# top_level.net
KiCad netlist of a schematic drawn in Altium Designer
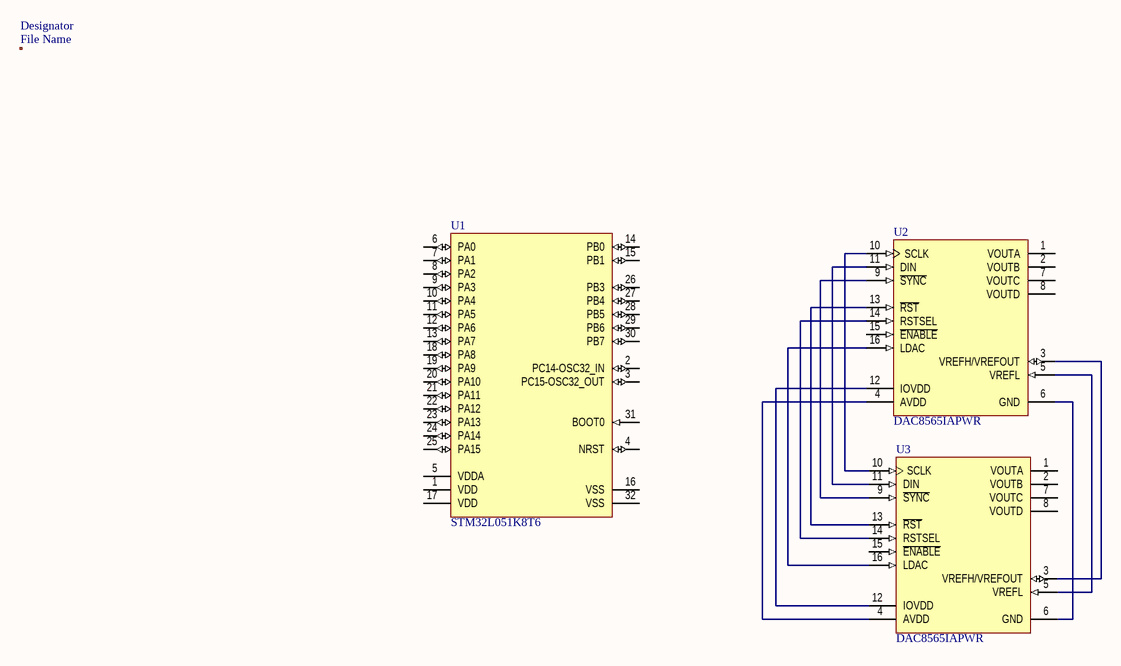
[diagram p0: top_level.SchDoc]

(export (version "E")
  (design (tool "Eeschema 10.0.6"))
  (components
    (comp (ref "U1")
      (value "STM32L051K8T6")
      (footprint "STM-LQFP32_L")
      (libsource (lib "Altium Content Vault") (part "STM-STM32L051-LQFP-32"))
    )
    (comp (ref "U2")
      (value "DAC8565IAPWR")
      (footprint "TI-PW16_L")
      (fields (field (name "MANUFACTURER") "Texas Instruments"))
      (libsource (lib "Altium Content Vault") (part "TI-DACXX65PW16"))
    )
    (comp (ref "U3")
      (value "DAC8565IAPWR")
      (footprint "TI-PW16_L")
      (fields (field (name "MANUFACTURER") "Texas Instruments"))
      (libsource (lib "Altium Content Vault") (part "TI-DACXX65PW16"))
    )
  )
  (nets
    (net (code "1") (name "Net-(U2-AVDD)") (class "Default")
      (node (ref "U2") (pin "4") (pinfunction "AVDD_4") (pintype "power_in"))
      (node (ref "U3") (pin "4") (pinfunction "AVDD_4") (pintype "power_in"))
    )
    (net (code "2") (name "Net-(U2-DIN)") (class "Default")
      (node (ref "U2") (pin "11") (pinfunction "DIN_11") (pintype "input"))
      (node (ref "U3") (pin "11") (pinfunction "DIN_11") (pintype "input"))
    )
    (net (code "3") (name "Net-(U2-GND)") (class "Default")
      (node (ref "U2") (pin "6") (pinfunction "GND_6") (pintype "power_in"))
      (node (ref "U3") (pin "6") (pinfunction "GND_6") (pintype "power_in"))
    )
    (net (code "4") (name "Net-(U2-IOVDD)") (class "Default")
      (node (ref "U2") (pin "12") (pinfunction "IOVDD_12") (pintype "power_in"))
      (node (ref "U3") (pin "12") (pinfunction "IOVDD_12") (pintype "power_in"))
    )
    (net (code "5") (name "Net-(U2-LDAC)") (class "Default")
      (node (ref "U2") (pin "16") (pinfunction "LDAC_16") (pintype "input"))
      (node (ref "U3") (pin "16") (pinfunction "LDAC_16") (pintype "input"))
    )
    (net (code "6") (name "Net-(U2-RSTSEL)") (class "Default")
      (node (ref "U2") (pin "14") (pinfunction "RSTSEL_14") (pintype "input"))
      (node (ref "U3") (pin "14") (pinfunction "RSTSEL_14") (pintype "input"))
    )
    (net (code "7") (name "Net-(U2-SCLK)") (class "Default")
      (node (ref "U2") (pin "10") (pinfunction "SCLK_10") (pintype "input"))
      (node (ref "U3") (pin "10") (pinfunction "SCLK_10") (pintype "input"))
    )
    (net (code "8") (name "Net-(U2-VREFH{slash}VREFOUT)") (class "Default")
      (node (ref "U2") (pin "3") (pinfunction "VREFH/VREFOUT_3") (pintype "bidirectional"))
      (node (ref "U3") (pin "3") (pinfunction "VREFH/VREFOUT_3") (pintype "bidirectional"))
    )
    (net (code "9") (name "Net-(U2-VREFL)") (class "Default")
      (node (ref "U2") (pin "5") (pinfunction "VREFL_5") (pintype "input"))
      (node (ref "U3") (pin "5") (pinfunction "VREFL_5") (pintype "input"))
    )
    (net (code "10") (name "Net-(U2-~{RST})") (class "Default")
      (node (ref "U2") (pin "13") (pinfunction "~{RST}_13") (pintype "input"))
      (node (ref "U3") (pin "13") (pinfunction "~{RST}_13") (pintype "input"))
    )
    (net (code "11") (name "Net-(U2-~{SYNC})") (class "Default")
      (node (ref "U2") (pin "9") (pinfunction "~{SYNC}_9") (pintype "input"))
      (node (ref "U3") (pin "9") (pinfunction "~{SYNC}_9") (pintype "input"))
    )
    (net (code "12") (name "unconnected-(U1-BOOT0-Pad31)") (class "Default")
      (node (ref "U1") (pin "31") (pinfunction "BOOT0_31") (pintype "input"))
    )
    (net (code "13") (name "unconnected-(U1-NRST-Pad4)") (class "Default")
      (node (ref "U1") (pin "4") (pinfunction "NRST_4") (pintype "bidirectional"))
    )
    (net (code "14") (name "unconnected-(U1-PA0-Pad6)") (class "Default")
      (node (ref "U1") (pin "6") (pinfunction "PA0_6") (pintype "bidirectional"))
    )
    (net (code "15") (name "unconnected-(U1-PA1-Pad7)") (class "Default")
      (node (ref "U1") (pin "7") (pinfunction "PA1_7") (pintype "bidirectional"))
    )
    (net (code "16") (name "unconnected-(U1-PA2-Pad8)") (class "Default")
      (node (ref "U1") (pin "8") (pinfunction "PA2_8") (pintype "bidirectional"))
    )
    (net (code "17") (name "unconnected-(U1-PA3-Pad9)") (class "Default")
      (node (ref "U1") (pin "9") (pinfunction "PA3_9") (pintype "bidirectional"))
    )
    (net (code "18") (name "unconnected-(U1-PA4-Pad10)") (class "Default")
      (node (ref "U1") (pin "10") (pinfunction "PA4_10") (pintype "bidirectional"))
    )
    (net (code "19") (name "unconnected-(U1-PA5-Pad11)") (class "Default")
      (node (ref "U1") (pin "11") (pinfunction "PA5_11") (pintype "bidirectional"))
    )
    (net (code "20") (name "unconnected-(U1-PA6-Pad12)") (class "Default")
      (node (ref "U1") (pin "12") (pinfunction "PA6_12") (pintype "bidirectional"))
    )
    (net (code "21") (name "unconnected-(U1-PA7-Pad13)") (class "Default")
      (node (ref "U1") (pin "13") (pinfunction "PA7_13") (pintype "bidirectional"))
    )
    (net (code "22") (name "unconnected-(U1-PA8-Pad18)") (class "Default")
      (node (ref "U1") (pin "18") (pinfunction "PA8_18") (pintype "bidirectional"))
    )
    (net (code "23") (name "unconnected-(U1-PA9-Pad19)") (class "Default")
      (node (ref "U1") (pin "19") (pinfunction "PA9_19") (pintype "bidirectional"))
    )
    (net (code "24") (name "unconnected-(U1-PA10-Pad20)") (class "Default")
      (node (ref "U1") (pin "20") (pinfunction "PA10_20") (pintype "bidirectional"))
    )
    (net (code "25") (name "unconnected-(U1-PA11-Pad21)") (class "Default")
      (node (ref "U1") (pin "21") (pinfunction "PA11_21") (pintype "bidirectional"))
    )
    (net (code "26") (name "unconnected-(U1-PA12-Pad22)") (class "Default")
      (node (ref "U1") (pin "22") (pinfunction "PA12_22") (pintype "bidirectional"))
    )
    (net (code "27") (name "unconnected-(U1-PA13-Pad23)") (class "Default")
      (node (ref "U1") (pin "23") (pinfunction "PA13_23") (pintype "bidirectional"))
    )
    (net (code "28") (name "unconnected-(U1-PA14-Pad24)") (class "Default")
      (node (ref "U1") (pin "24") (pinfunction "PA14_24") (pintype "bidirectional"))
    )
    (net (code "29") (name "unconnected-(U1-PA15-Pad25)") (class "Default")
      (node (ref "U1") (pin "25") (pinfunction "PA15_25") (pintype "bidirectional"))
    )
    (net (code "30") (name "unconnected-(U1-PB0-Pad14)") (class "Default")
      (node (ref "U1") (pin "14") (pinfunction "PB0_14") (pintype "bidirectional"))
    )
    (net (code "31") (name "unconnected-(U1-PB1-Pad15)") (class "Default")
      (node (ref "U1") (pin "15") (pinfunction "PB1_15") (pintype "bidirectional"))
    )
    (net (code "32") (name "unconnected-(U1-PB3-Pad26)") (class "Default")
      (node (ref "U1") (pin "26") (pinfunction "PB3_26") (pintype "bidirectional"))
    )
    (net (code "33") (name "unconnected-(U1-PB4-Pad27)") (class "Default")
      (node (ref "U1") (pin "27") (pinfunction "PB4_27") (pintype "bidirectional"))
    )
    (net (code "34") (name "unconnected-(U1-PB5-Pad28)") (class "Default")
      (node (ref "U1") (pin "28") (pinfunction "PB5_28") (pintype "bidirectional"))
    )
    (net (code "35") (name "unconnected-(U1-PB6-Pad29)") (class "Default")
      (node (ref "U1") (pin "29") (pinfunction "PB6_29") (pintype "bidirectional"))
    )
    (net (code "36") (name "unconnected-(U1-PB7-Pad30)") (class "Default")
      (node (ref "U1") (pin "30") (pinfunction "PB7_30") (pintype "bidirectional"))
    )
    (net (code "37") (name "unconnected-(U1-PC14-OSC32_IN-Pad2)") (class "Default")
      (node (ref "U1") (pin "2") (pinfunction "PC14-OSC32_IN_2") (pintype "bidirectional"))
    )
    (net (code "38") (name "unconnected-(U1-PC15-OSC32_OUT-Pad3)") (class "Default")
      (node (ref "U1") (pin "3") (pinfunction "PC15-OSC32_OUT_3") (pintype "bidirectional"))
    )
    (net (code "39") (name "unconnected-(U1-VDD-Pad1)") (class "Default")
      (node (ref "U1") (pin "1") (pinfunction "VDD_1") (pintype "power_in"))
    )
    (net (code "40") (name "unconnected-(U1-VDD-Pad17)") (class "Default")
      (node (ref "U1") (pin "17") (pinfunction "VDD_17") (pintype "power_in"))
    )
    (net (code "41") (name "unconnected-(U1-VDDA-Pad5)") (class "Default")
      (node (ref "U1") (pin "5") (pinfunction "VDDA_5") (pintype "power_in"))
    )
    (net (code "42") (name "unconnected-(U1-VSS-Pad16)") (class "Default")
      (node (ref "U1") (pin "16") (pinfunction "VSS_16") (pintype "power_in"))
    )
    (net (code "43") (name "unconnected-(U1-VSS-Pad32)") (class "Default")
      (node (ref "U1") (pin "32") (pinfunction "VSS_32") (pintype "power_in"))
    )
    (net (code "44") (name "unconnected-(U2-VOUTA-Pad1)") (class "Default")
      (node (ref "U2") (pin "1") (pinfunction "VOUTA_1") (pintype "tri_state"))
    )
    (net (code "45") (name "unconnected-(U2-VOUTB-Pad2)") (class "Default")
      (node (ref "U2") (pin "2") (pinfunction "VOUTB_2") (pintype "tri_state"))
    )
    (net (code "46") (name "unconnected-(U2-VOUTC-Pad7)") (class "Default")
      (node (ref "U2") (pin "7") (pinfunction "VOUTC_7") (pintype "tri_state"))
    )
    (net (code "47") (name "unconnected-(U2-VOUTD-Pad8)") (class "Default")
      (node (ref "U2") (pin "8") (pinfunction "VOUTD_8") (pintype "tri_state"))
    )
    (net (code "48") (name "unconnected-(U2-~{ENABLE}-Pad15)") (class "Default")
      (node (ref "U2") (pin "15") (pinfunction "~{ENABLE}_15") (pintype "input"))
    )
    (net (code "49") (name "unconnected-(U3-VOUTA-Pad1)") (class "Default")
      (node (ref "U3") (pin "1") (pinfunction "VOUTA_1") (pintype "tri_state"))
    )
    (net (code "50") (name "unconnected-(U3-VOUTB-Pad2)") (class "Default")
      (node (ref "U3") (pin "2") (pinfunction "VOUTB_2") (pintype "tri_state"))
    )
    (net (code "51") (name "unconnected-(U3-VOUTC-Pad7)") (class "Default")
      (node (ref "U3") (pin "7") (pinfunction "VOUTC_7") (pintype "tri_state"))
    )
    (net (code "52") (name "unconnected-(U3-VOUTD-Pad8)") (class "Default")
      (node (ref "U3") (pin "8") (pinfunction "VOUTD_8") (pintype "tri_state"))
    )
    (net (code "53") (name "unconnected-(U3-~{ENABLE}-Pad15)") (class "Default")
      (node (ref "U3") (pin "15") (pinfunction "~{ENABLE}_15") (pintype "input"))
    )
  )
)
